# v0_1.net
KiCad netlist of a schematic drawn in EAGLE
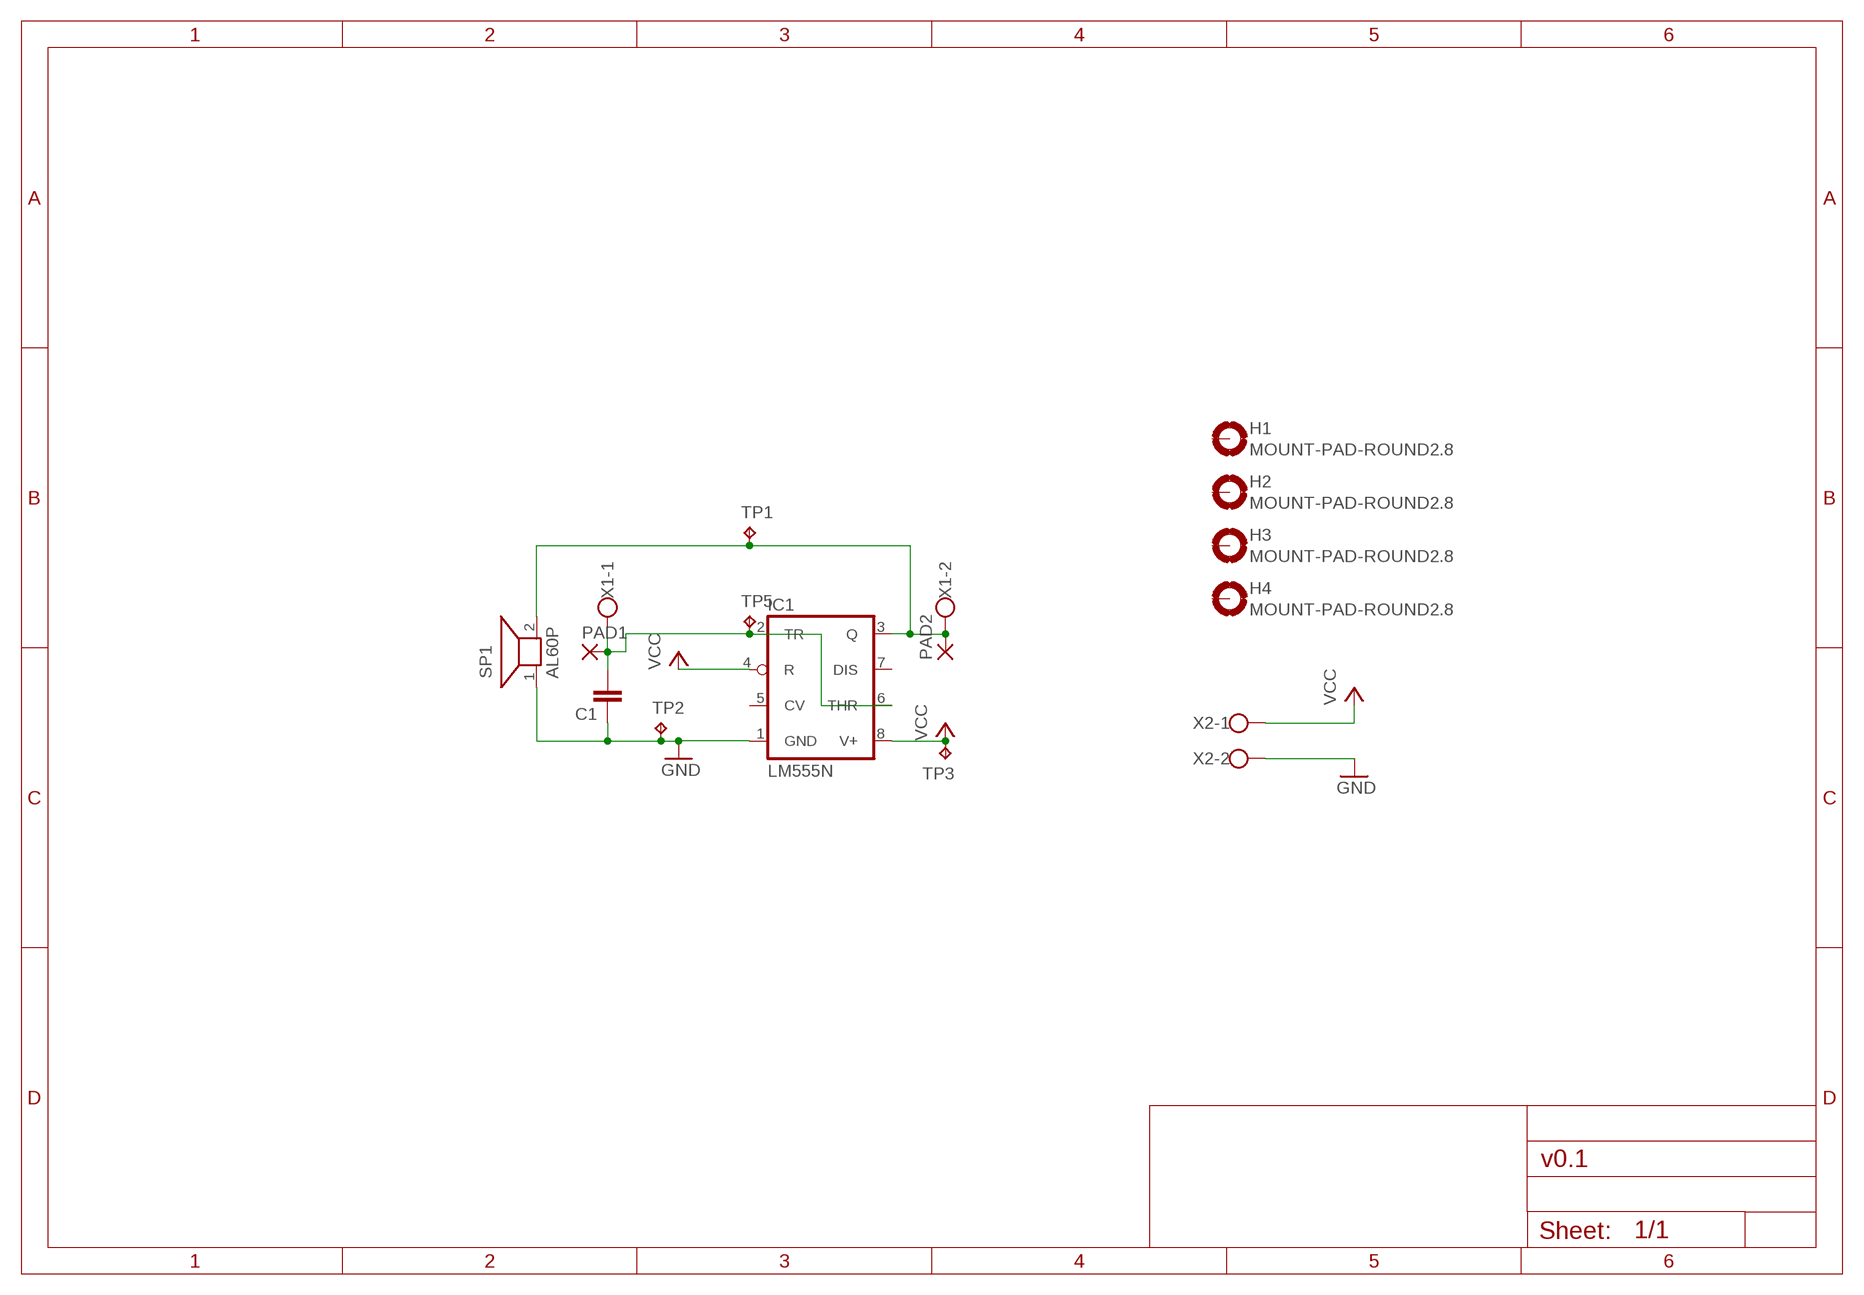
[diagram p0: schematic, sheet 1]

(export (version "E")
  (design (tool "Eeschema 10.0.6"))
  (components
    (comp (ref "C1")
      (value "C2,5-3")
      (footprint "eagle-import:C2.5-3")
      (libsource (lib "eagle-import") (part "C2,5-3"))
    )
    (comp (ref "H1")
      (value "MOUNT-PAD-ROUND2.8")
      (footprint "eagle-import:2,8-PAD")
      (libsource (lib "eagle-import") (part "MOUNT-PAD-ROUND2.8"))
    )
    (comp (ref "H2")
      (value "MOUNT-PAD-ROUND2.8")
      (footprint "eagle-import:2,8-PAD")
      (libsource (lib "eagle-import") (part "MOUNT-PAD-ROUND2.8"))
    )
    (comp (ref "H3")
      (value "MOUNT-PAD-ROUND2.8")
      (footprint "eagle-import:2,8-PAD")
      (libsource (lib "eagle-import") (part "MOUNT-PAD-ROUND2.8"))
    )
    (comp (ref "H4")
      (value "MOUNT-PAD-ROUND2.8")
      (footprint "eagle-import:2,8-PAD")
      (libsource (lib "eagle-import") (part "MOUNT-PAD-ROUND2.8"))
    )
    (comp (ref "IC1")
      (value "LM555N")
      (footprint "eagle-import:DIL08")
      (libsource (lib "eagle-import") (part "555NLM"))
    )
    (comp (ref "PAD1")
      (value "SMD5")
      (footprint "eagle-import:SMD2,54-5,08")
      (libsource (lib "eagle-import") (part "SMD5"))
    )
    (comp (ref "PAD2")
      (value "SMD5")
      (footprint "eagle-import:SMD2,54-5,08")
      (libsource (lib "eagle-import") (part "SMD5"))
    )
    (comp (ref "SP1")
      (value "AL60P")
      (footprint "eagle-import:AL60P")
      (libsource (lib "eagle-import") (part "AL60P"))
    )
    (comp (ref "TP1")
      (value "TPB1,27")
      (footprint "eagle-import:B1,27")
      (libsource (lib "eagle-import") (part "TPB1,27"))
    )
    (comp (ref "TP2")
      (value "TPB1,27")
      (footprint "eagle-import:B1,27")
      (libsource (lib "eagle-import") (part "TPB1,27"))
    )
    (comp (ref "TP3")
      (value "TPB1,27")
      (footprint "eagle-import:B1,27")
      (libsource (lib "eagle-import") (part "TPB1,27"))
    )
    (comp (ref "TP5")
      (value "TPB1,27")
      (footprint "eagle-import:B1,27")
      (libsource (lib "eagle-import") (part "TPB1,27"))
    )
    (comp (ref "X1")
      (value "W237-102")
      (footprint "eagle-import:W237-102")
      (fields (field (name "MPN") "237-102"))
      (libsource (lib "eagle-import") (part "W237-102"))
    )
    (comp (ref "X2")
      (value "W237-102")
      (footprint "eagle-import:W237-102")
      (fields (field (name "MPN") "237-102"))
      (libsource (lib "eagle-import") (part "W237-102"))
    )
  )
  (nets
    (net (code "1") (name "GND") (class "Default")
      (node (ref "C1") (pin "1") (pinfunction "1_1") (pintype "passive"))
      (node (ref "IC1") (pin "1") (pinfunction "GND_1") (pintype "power_in"))
      (node (ref "SP1") (pin "1") (pinfunction "1_1") (pintype "passive"))
      (node (ref "TP2") (pin "TP") (pinfunction "TP_TP") (pintype "input"))
      (node (ref "X2") (pin "2") (pinfunction "KL_2") (pintype "passive"))
    )
    (net (code "2") (name "Net-(IC1-Q)") (class "Default")
      (node (ref "IC1") (pin "3") (pinfunction "Q_3") (pintype "output"))
      (node (ref "PAD2") (pin "1") (pinfunction "P_1") (pintype "passive"))
      (node (ref "SP1") (pin "2") (pinfunction "2_2") (pintype "passive"))
      (node (ref "TP1") (pin "TP") (pinfunction "TP_TP") (pintype "input"))
      (node (ref "X1") (pin "2") (pinfunction "KL_2") (pintype "passive"))
    )
    (net (code "3") (name "Net-(IC1-THR)") (class "Default")
      (node (ref "C1") (pin "2") (pinfunction "2_2") (pintype "passive"))
      (node (ref "IC1") (pin "2") (pinfunction "TR_2") (pintype "input"))
      (node (ref "IC1") (pin "6") (pinfunction "THR_6") (pintype "input"))
      (node (ref "PAD1") (pin "1") (pinfunction "P_1") (pintype "passive"))
      (node (ref "TP5") (pin "TP") (pinfunction "TP_TP") (pintype "input"))
      (node (ref "X1") (pin "1") (pinfunction "KL_1") (pintype "passive"))
    )
    (net (code "4") (name "VCC") (class "Default")
      (node (ref "IC1") (pin "4") (pinfunction "R_4") (pintype "input"))
      (node (ref "IC1") (pin "8") (pinfunction "V+_8") (pintype "power_in"))
      (node (ref "TP3") (pin "TP") (pinfunction "TP_TP") (pintype "input"))
      (node (ref "X2") (pin "1") (pinfunction "KL_1") (pintype "passive"))
    )
    (net (code "5") (name "unconnected-(H1-MOUNT-PadB2,8)") (class "Default")
      (node (ref "H1") (pin "B2,8") (pinfunction "MOUNT_B2,8") (pintype "passive"))
    )
    (net (code "6") (name "unconnected-(H2-MOUNT-PadB2,8)") (class "Default")
      (node (ref "H2") (pin "B2,8") (pinfunction "MOUNT_B2,8") (pintype "passive"))
    )
    (net (code "7") (name "unconnected-(H3-MOUNT-PadB2,8)") (class "Default")
      (node (ref "H3") (pin "B2,8") (pinfunction "MOUNT_B2,8") (pintype "passive"))
    )
    (net (code "8") (name "unconnected-(H4-MOUNT-PadB2,8)") (class "Default")
      (node (ref "H4") (pin "B2,8") (pinfunction "MOUNT_B2,8") (pintype "passive"))
    )
    (net (code "9") (name "unconnected-(IC1-CV-Pad5)") (class "Default")
      (node (ref "IC1") (pin "5") (pinfunction "CV_5") (pintype "input"))
    )
    (net (code "10") (name "unconnected-(IC1-DIS-Pad7)") (class "Default")
      (node (ref "IC1") (pin "7") (pinfunction "DIS_7") (pintype "input"))
    )
  )
)
